# devboard-8_0.net
KiCad netlist of a schematic drawn in EAGLE
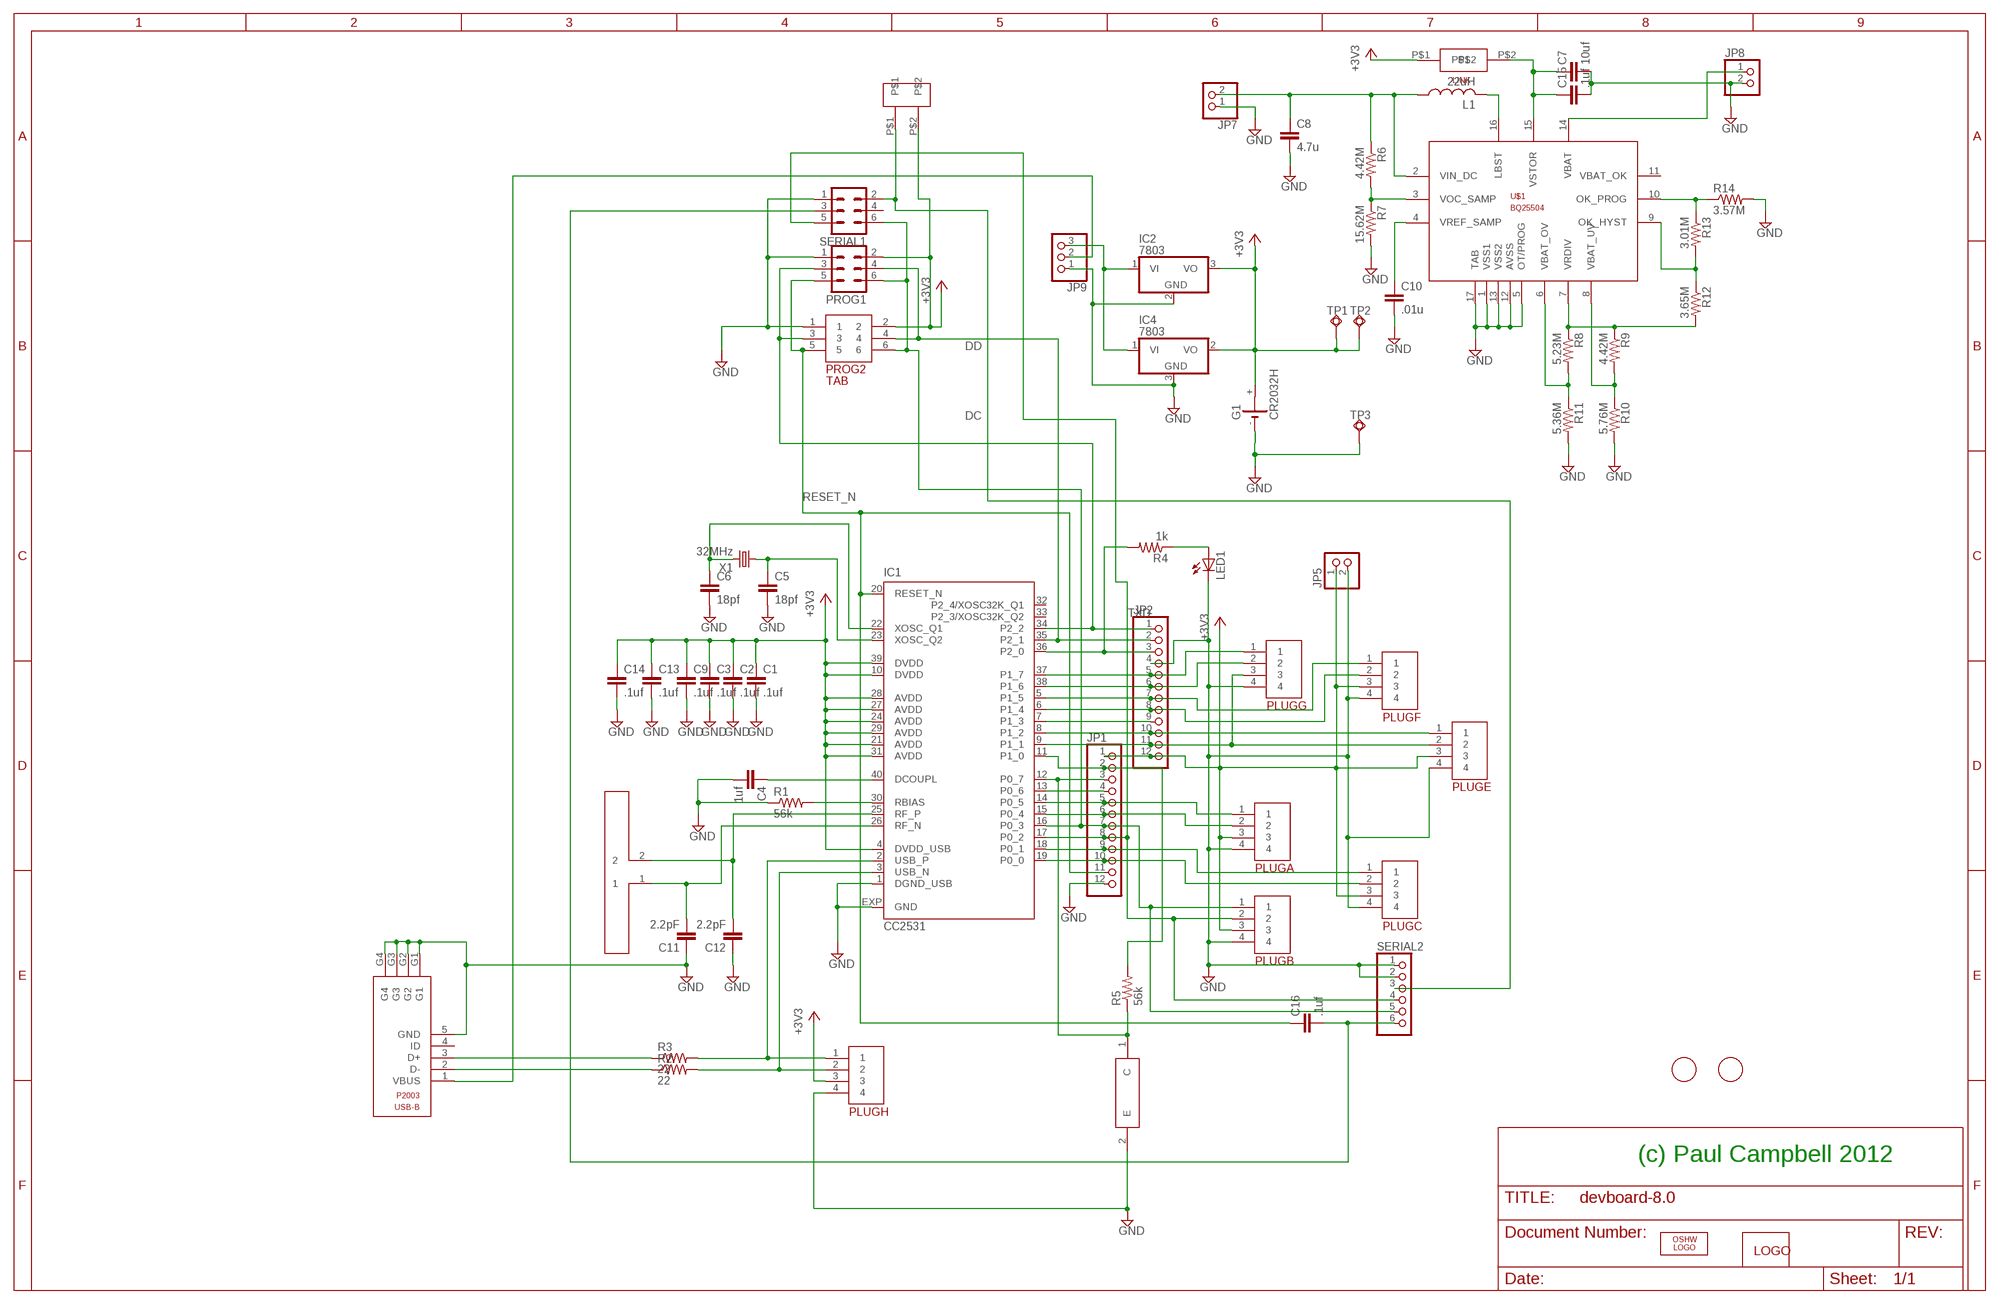
[diagram p0: schematic, sheet 1]

(export (version "E")
  (design (tool "Eeschema 10.0.6"))
  (components
    (comp (ref "C1")
      (value ".1uf")
      (footprint "eagle-import:C0603K")
      (libsource (lib "eagle-import") (part "C-EUC0603K"))
    )
    (comp (ref "C2")
      (value ".1uf")
      (footprint "eagle-import:C0603K")
      (libsource (lib "eagle-import") (part "C-EUC0603K"))
    )
    (comp (ref "C3")
      (value ".1uf")
      (footprint "eagle-import:C0603K")
      (libsource (lib "eagle-import") (part "C-EUC0603K"))
    )
    (comp (ref "C4")
      (value "1uf")
      (footprint "eagle-import:C0603K")
      (libsource (lib "eagle-import") (part "C-EUC0603K"))
    )
    (comp (ref "C5")
      (value "18pf")
      (footprint "eagle-import:C0603")
      (libsource (lib "eagle-import") (part "C-EUC0603"))
    )
    (comp (ref "C6")
      (value "18pf")
      (footprint "eagle-import:C0603")
      (libsource (lib "eagle-import") (part "C-EUC0603"))
    )
    (comp (ref "C7")
      (value "10uf")
      (footprint "eagle-import:C1206")
      (libsource (lib "eagle-import") (part "C-EUC1206"))
    )
    (comp (ref "C8")
      (value "4.7u")
      (footprint "eagle-import:C0603")
      (libsource (lib "eagle-import") (part "C-EUC0603"))
    )
    (comp (ref "C9")
      (value ".1uf")
      (footprint "eagle-import:C0603K")
      (libsource (lib "eagle-import") (part "C-EUC0603K"))
    )
    (comp (ref "C10")
      (value ".01u")
      (footprint "eagle-import:C0603")
      (libsource (lib "eagle-import") (part "C-EUC0603"))
    )
    (comp (ref "C11")
      (value "2.2pF")
      (footprint "eagle-import:C0402")
      (libsource (lib "eagle-import") (part "C-EUC0402"))
    )
    (comp (ref "C12")
      (value "2.2pF")
      (footprint "eagle-import:C0402")
      (libsource (lib "eagle-import") (part "C-EUC0402"))
    )
    (comp (ref "C13")
      (value ".1uf")
      (footprint "eagle-import:C0603K")
      (libsource (lib "eagle-import") (part "C-EUC0603K"))
    )
    (comp (ref "C14")
      (value ".1uf")
      (footprint "eagle-import:C0603K")
      (libsource (lib "eagle-import") (part "C-EUC0603K"))
    )
    (comp (ref "C15")
      (value ".1uf")
      (footprint "eagle-import:C0603K")
      (libsource (lib "eagle-import") (part "C-EUC0603K"))
    )
    (comp (ref "C16")
      (value ".1uf")
      (footprint "eagle-import:C0603K")
      (libsource (lib "eagle-import") (part "C-EUC0603K"))
    )
    (comp (ref "G1")
      (value "CR2032H")
      (footprint "eagle-import:CR2032H")
      (libsource (lib "eagle-import") (part "CR2032H"))
    )
    (comp (ref "IC1")
      (value "CC2531")
      (footprint "eagle-import:RHA_S-PVQFN-N40")
      (fields (field (name "MPN") "CC2531F256RHAT"))
      (libsource (lib "eagle-import") (part "CC2531"))
    )
    (comp (ref "IC2")
      (value "7803")
      (footprint "eagle-import:TO220V")
      (libsource (lib "eagle-import") (part "78TV05"))
    )
    (comp (ref "IC4")
      (value "7803")
      (footprint "eagle-import:TO252")
      (libsource (lib "eagle-import") (part "78DT05"))
    )
    (comp (ref "JP1")
      (value "PINHD-1X12-CB")
      (footprint "eagle-import:1X12-CB")
      (libsource (lib "eagle-import") (part "PINHD-1X12-CB"))
    )
    (comp (ref "JP2")
      (value "PINHD-1X12-CB")
      (footprint "eagle-import:1X12-CB")
      (libsource (lib "eagle-import") (part "PINHD-1X12-CB"))
    )
    (comp (ref "JP5")
      (value "PINHD-1X2")
      (footprint "eagle-import:1X02")
      (libsource (lib "eagle-import") (part "PINHD-1X2"))
    )
    (comp (ref "JP7")
      (value "PINHD-1X2")
      (footprint "eagle-import:1X02")
      (libsource (lib "eagle-import") (part "PINHD-1X2"))
    )
    (comp (ref "JP8")
      (value "PINHD-1X2")
      (footprint "eagle-import:1X02")
      (libsource (lib "eagle-import") (part "PINHD-1X2"))
    )
    (comp (ref "JP9")
      (value "PINHD-1X3")
      (footprint "eagle-import:1X03")
      (libsource (lib "eagle-import") (part "PINHD-1X3"))
    )
    (comp (ref "L1")
      (value "22uH")
      (footprint "eagle-import:L2012C")
      (libsource (lib "eagle-import") (part "L-USL2012C"))
    )
    (comp (ref "LED1")
      (value "LEDCHIP-LED0603")
      (footprint "eagle-import:CHIP-LED0603")
      (libsource (lib "eagle-import") (part "LEDCHIP-LED0603"))
    )
    (comp (ref "LOGO1")
      (value "OSHW_LOGO_FILLX0100-NT")
      (footprint "eagle-import:OSHW_FILLX100_NOTEXT")
      (libsource (lib "eagle-import") (part "OSHW_LOGO_FILLX0100-NT"))
    )
    (comp (ref "P2003")
      (value "FCI1018193-USBB")
      (footprint "eagle-import:FCI1018193-USBB")
      (libsource (lib "eagle-import") (part "FCI1018193-USBB"))
    )
    (comp (ref "PLUGA")
      (value "PIN4")
      (footprint "eagle-import:PIN4-2MM")
      (libsource (lib "eagle-import") (part "PIN4"))
    )
    (comp (ref "PLUGB")
      (value "PIN4")
      (footprint "eagle-import:PIN4-2MM")
      (libsource (lib "eagle-import") (part "PIN4"))
    )
    (comp (ref "PLUGC")
      (value "PIN4")
      (footprint "eagle-import:PIN4-2MM")
      (libsource (lib "eagle-import") (part "PIN4"))
    )
    (comp (ref "PLUGE")
      (value "PIN4")
      (footprint "eagle-import:PIN4-2MM")
      (libsource (lib "eagle-import") (part "PIN4"))
    )
    (comp (ref "PLUGF")
      (value "PIN4")
      (footprint "eagle-import:PIN4-2MM")
      (libsource (lib "eagle-import") (part "PIN4"))
    )
    (comp (ref "PLUGG")
      (value "PIN4")
      (footprint "eagle-import:PIN4-2MM")
      (libsource (lib "eagle-import") (part "PIN4"))
    )
    (comp (ref "PLUGH")
      (value "PIN4")
      (footprint "eagle-import:PIN4-2MM")
      (libsource (lib "eagle-import") (part "PIN4"))
    )
    (comp (ref "PROG1")
      (value "MA03-2")
      (footprint "eagle-import:MA03-2")
      (libsource (lib "eagle-import") (part "MA03-2"))
    )
    (comp (ref "PROG2")
      (value "TAB")
      (footprint "eagle-import:TAG")
      (libsource (lib "eagle-import") (part "TAB"))
    )
    (comp (ref "Q1")
      (value "KDT")
      (footprint "eagle-import:KDT")
      (libsource (lib "eagle-import") (part "KDT"))
    )
    (comp (ref "R1")
      (value "56k")
      (footprint "eagle-import:R0603")
      (libsource (lib "eagle-import") (part "R-US_R0603"))
    )
    (comp (ref "R2")
      (value "22")
      (footprint "eagle-import:R0603")
      (libsource (lib "eagle-import") (part "R-US_R0603"))
    )
    (comp (ref "R3")
      (value "22")
      (footprint "eagle-import:R0603")
      (libsource (lib "eagle-import") (part "R-US_R0603"))
    )
    (comp (ref "R4")
      (value "1k")
      (footprint "eagle-import:R0603")
      (libsource (lib "eagle-import") (part "R-US_R0603"))
    )
    (comp (ref "R5")
      (value "56k")
      (footprint "eagle-import:R0603")
      (libsource (lib "eagle-import") (part "R-US_R0603"))
    )
    (comp (ref "R6")
      (value "4.42M")
      (footprint "eagle-import:R0603")
      (libsource (lib "eagle-import") (part "R-US_R0603"))
    )
    (comp (ref "R7")
      (value "15.62M")
      (footprint "eagle-import:R0603")
      (libsource (lib "eagle-import") (part "R-US_R0603"))
    )
    (comp (ref "R8")
      (value "5.23M")
      (footprint "eagle-import:R0603")
      (libsource (lib "eagle-import") (part "R-US_R0603"))
    )
    (comp (ref "R9")
      (value "4.42M")
      (footprint "eagle-import:R0603")
      (libsource (lib "eagle-import") (part "R-US_R0603"))
    )
    (comp (ref "R10")
      (value "5.76M")
      (footprint "eagle-import:R0603")
      (libsource (lib "eagle-import") (part "R-US_R0603"))
    )
    (comp (ref "R11")
      (value "5.36M")
      (footprint "eagle-import:R0603")
      (libsource (lib "eagle-import") (part "R-US_R0603"))
    )
    (comp (ref "R12")
      (value "3.65M")
      (footprint "eagle-import:R0603")
      (libsource (lib "eagle-import") (part "R-US_R0603"))
    )
    (comp (ref "R13")
      (value "3.01M")
      (footprint "eagle-import:R0603")
      (libsource (lib "eagle-import") (part "R-US_R0603"))
    )
    (comp (ref "R14")
      (value "3.57M")
      (footprint "eagle-import:R0603")
      (libsource (lib "eagle-import") (part "R-US_R0603"))
    )
    (comp (ref "SERIAL-POWER")
      (value "2-PAD")
      (footprint "eagle-import:2-PAD")
      (libsource (lib "eagle-import") (part "2-PAD"))
    )
    (comp (ref "SERIAL1")
      (value "MA03-2")
      (footprint "eagle-import:MA03-2")
      (libsource (lib "eagle-import") (part "MA03-2"))
    )
    (comp (ref "SERIAL2")
      (value "PINHD-1X6")
      (footprint "eagle-import:1X06")
      (libsource (lib "eagle-import") (part "PINHD-1X6"))
    )
    (comp (ref "TP1")
      (value "TPSQPAD1-13")
      (footprint "eagle-import:P1-13")
      (libsource (lib "eagle-import") (part "TPSQPAD1-13"))
    )
    (comp (ref "TP2")
      (value "TPSQPAD1-13")
      (footprint "eagle-import:P1-13")
      (libsource (lib "eagle-import") (part "TPSQPAD1-13"))
    )
    (comp (ref "TP3")
      (value "TPSQPAD1-13")
      (footprint "eagle-import:P1-13")
      (libsource (lib "eagle-import") (part "TPSQPAD1-13"))
    )
    (comp (ref "U$1")
      (value "BQ25504")
      (footprint "eagle-import:QF16")
      (libsource (lib "eagle-import") (part "BQ25504"))
    )
    (comp (ref "U$2")
      (value "FIDUCIAL")
      (footprint "eagle-import:FIDUCIAL_1MM")
      (libsource (lib "eagle-import") (part "FIDUCIAL"))
    )
    (comp (ref "U$3")
      (value "DIPOLEDIPOLE1")
      (footprint "eagle-import:DIPOLE")
      (libsource (lib "eagle-import") (part "DIPOLEDIPOLE1"))
    )
    (comp (ref "U$4")
      (value "2-PAD-LINK")
      (footprint "eagle-import:2-PAD-LINK")
      (libsource (lib "eagle-import") (part "2-PAD-LINK"))
    )
    (comp (ref "U$5")
      (value "MOONBASE-LOGO")
      (footprint "eagle-import:MOONBASE-LOGO")
      (libsource (lib "eagle-import") (part "MOONBASE-LOGO"))
    )
    (comp (ref "U$18")
      (value "FIDUCIAL")
      (footprint "eagle-import:FIDUCIAL_1MM")
      (libsource (lib "eagle-import") (part "FIDUCIAL"))
    )
    (comp (ref "X1")
      (value "32MHz")
      (footprint "eagle-import:SM49")
      (libsource (lib "eagle-import") (part "CRYSTALSM49"))
    )
  )
  (nets
    (net (code "1") (name "+3V3") (class "Default")
      (node (ref "C1") (pin "1") (pinfunction "1_1") (pintype "passive"))
      (node (ref "C13") (pin "1") (pinfunction "1_1") (pintype "passive"))
      (node (ref "C14") (pin "1") (pinfunction "1_1") (pintype "passive"))
      (node (ref "C2") (pin "1") (pinfunction "1_1") (pintype "passive"))
      (node (ref "C3") (pin "1") (pinfunction "1_1") (pintype "passive"))
      (node (ref "C9") (pin "1") (pinfunction "1_1") (pintype "passive"))
      (node (ref "G1") (pin "+") (pinfunction "+_+") (pintype "passive"))
      (node (ref "IC1") (pin "10") (pinfunction "DVDD_10") (pintype "power_in"))
      (node (ref "IC1") (pin "21") (pinfunction "AVDD_21") (pintype "power_in"))
      (node (ref "IC1") (pin "24") (pinfunction "AVDD_24") (pintype "power_in"))
      (node (ref "IC1") (pin "27") (pinfunction "AVDD_27") (pintype "power_in"))
      (node (ref "IC1") (pin "28") (pinfunction "AVDD_28") (pintype "power_in"))
      (node (ref "IC1") (pin "29") (pinfunction "AVDD_29") (pintype "power_in"))
      (node (ref "IC1") (pin "31") (pinfunction "AVDD_31") (pintype "power_in"))
      (node (ref "IC1") (pin "39") (pinfunction "DVDD_39") (pintype "power_in"))
      (node (ref "IC1") (pin "4") (pinfunction "DVDD_USB_4") (pintype "power_in"))
      (node (ref "IC2") (pin "3") (pinfunction "VO_3") (pintype "passive"))
      (node (ref "IC4") (pin "2") (pinfunction "VO_2") (pintype "passive"))
      (node (ref "JP1") (pin "1") (pinfunction "1_1") (pintype "passive"))
      (node (ref "JP2") (pin "12") (pinfunction "12_12") (pintype "passive"))
      (node (ref "JP5") (pin "1") (pinfunction "1_1") (pintype "passive"))
      (node (ref "PLUGA") (pin "3") (pinfunction "3_3") (pintype "bidirectional"))
      (node (ref "PLUGB") (pin "3") (pinfunction "3_3") (pintype "bidirectional"))
      (node (ref "PLUGC") (pin "3") (pinfunction "3_3") (pintype "bidirectional"))
      (node (ref "PLUGE") (pin "3") (pinfunction "3_3") (pintype "bidirectional"))
      (node (ref "PLUGF") (pin "3") (pinfunction "3_3") (pintype "bidirectional"))
      (node (ref "PLUGH") (pin "3") (pinfunction "3_3") (pintype "bidirectional"))
      (node (ref "PROG1") (pin "2") (pinfunction "2_2") (pintype "passive"))
      (node (ref "PROG2") (pin "2") (pinfunction "2_2") (pintype "bidirectional"))
      (node (ref "SERIAL-POWER") (pin "P$2") (pinfunction "P$2_P$2") (pintype "bidirectional"))
      (node (ref "TP1") (pin "TP") (pinfunction "TP_TP") (pintype "input"))
      (node (ref "TP2") (pin "TP") (pinfunction "TP_TP") (pintype "input"))
      (node (ref "U$4") (pin "P$1") (pinfunction "P$1_P$1") (pintype "bidirectional"))
    )
    (net (code "2") (name "/DC") (class "Default")
      (node (ref "IC1") (pin "34") (pinfunction "P2_2_34") (pintype "bidirectional"))
      (node (ref "JP2") (pin "1") (pinfunction "1_1") (pintype "passive"))
      (node (ref "PROG1") (pin "3") (pinfunction "3_3") (pintype "passive"))
      (node (ref "PROG2") (pin "3") (pinfunction "3_3") (pintype "bidirectional"))
    )
    (net (code "3") (name "/DD") (class "Default")
      (node (ref "IC1") (pin "35") (pinfunction "P2_1_35") (pintype "bidirectional"))
      (node (ref "JP2") (pin "2") (pinfunction "2_2") (pintype "passive"))
      (node (ref "PROG1") (pin "4") (pinfunction "4_4") (pintype "passive"))
      (node (ref "PROG2") (pin "4") (pinfunction "4_4") (pintype "bidirectional"))
    )
    (net (code "4") (name "/RESET_N") (class "Default")
      (node (ref "C16") (pin "1") (pinfunction "1_1") (pintype "passive"))
      (node (ref "IC1") (pin "20") (pinfunction "RESET_N_20") (pintype "input"))
      (node (ref "JP1") (pin "11") (pinfunction "11_11") (pintype "passive"))
      (node (ref "PROG1") (pin "5") (pinfunction "5_5") (pintype "passive"))
      (node (ref "PROG2") (pin "5") (pinfunction "5_5") (pintype "bidirectional"))
    )
    (net (code "5") (name "/TXD") (class "Default")
      (node (ref "IC1") (pin "16") (pinfunction "P0_3_16") (pintype "bidirectional"))
      (node (ref "JP1") (pin "7") (pinfunction "7_7") (pintype "passive"))
      (node (ref "PLUGB") (pin "1") (pinfunction "1_1") (pintype "bidirectional"))
      (node (ref "PROG1") (pin "6") (pinfunction "6_6") (pintype "passive"))
      (node (ref "PROG2") (pin "6") (pinfunction "6_6") (pintype "bidirectional"))
      (node (ref "SERIAL1") (pin "6") (pinfunction "6_6") (pintype "passive"))
      (node (ref "SERIAL2") (pin "5") (pinfunction "5_5") (pintype "passive"))
    )
    (net (code "6") (name "GND") (class "Default")
      (node (ref "C1") (pin "2") (pinfunction "2_2") (pintype "passive"))
      (node (ref "C10") (pin "2") (pinfunction "2_2") (pintype "passive"))
      (node (ref "C11") (pin "1") (pinfunction "1_1") (pintype "passive"))
      (node (ref "C12") (pin "1") (pinfunction "1_1") (pintype "passive"))
      (node (ref "C13") (pin "2") (pinfunction "2_2") (pintype "passive"))
      (node (ref "C14") (pin "2") (pinfunction "2_2") (pintype "passive"))
      (node (ref "C15") (pin "2") (pinfunction "2_2") (pintype "passive"))
      (node (ref "C2") (pin "2") (pinfunction "2_2") (pintype "passive"))
      (node (ref "C3") (pin "2") (pinfunction "2_2") (pintype "passive"))
      (node (ref "C4") (pin "2") (pinfunction "2_2") (pintype "passive"))
      (node (ref "C5") (pin "2") (pinfunction "2_2") (pintype "passive"))
      (node (ref "C6") (pin "2") (pinfunction "2_2") (pintype "passive"))
      (node (ref "C7") (pin "2") (pinfunction "2_2") (pintype "passive"))
      (node (ref "C8") (pin "2") (pinfunction "2_2") (pintype "passive"))
      (node (ref "C9") (pin "2") (pinfunction "2_2") (pintype "passive"))
      (node (ref "G1") (pin "-") (pinfunction "-_-") (pintype "passive"))
      (node (ref "IC1") (pin "1") (pinfunction "DGND_USB_1") (pintype "power_in"))
      (node (ref "IC1") (pin "EXP") (pinfunction "GND_EXP") (pintype "passive"))
      (node (ref "IC2") (pin "2") (pinfunction "GND_2") (pintype "passive"))
      (node (ref "IC4") (pin "3") (pinfunction "GND_3") (pintype "passive"))
      (node (ref "JP1") (pin "12") (pinfunction "12_12") (pintype "passive"))
      (node (ref "JP2") (pin "4") (pinfunction "4_4") (pintype "passive"))
      (node (ref "JP5") (pin "2") (pinfunction "2_2") (pintype "passive"))
      (node (ref "JP7") (pin "1") (pinfunction "1_1") (pintype "passive"))
      (node (ref "JP8") (pin "2") (pinfunction "2_2") (pintype "passive"))
      (node (ref "JP9") (pin "1") (pinfunction "1_1") (pintype "passive"))
      (node (ref "LED1") (pin "C") (pinfunction "C_C") (pintype "passive"))
      (node (ref "P2003") (pin "5") (pinfunction "GND_5") (pintype "bidirectional"))
      (node (ref "P2003") (pin "G1") (pinfunction "G1_G1") (pintype "bidirectional"))
      (node (ref "P2003") (pin "G2") (pinfunction "G2_G2") (pintype "bidirectional"))
      (node (ref "P2003") (pin "G3") (pinfunction "G3_G3") (pintype "bidirectional"))
      (node (ref "P2003") (pin "G4") (pinfunction "G4_G4") (pintype "bidirectional"))
      (node (ref "PLUGA") (pin "4") (pinfunction "4_4") (pintype "bidirectional"))
      (node (ref "PLUGB") (pin "4") (pinfunction "4_4") (pintype "bidirectional"))
      (node (ref "PLUGC") (pin "4") (pinfunction "4_4") (pintype "bidirectional"))
      (node (ref "PLUGE") (pin "4") (pinfunction "4_4") (pintype "bidirectional"))
      (node (ref "PLUGF") (pin "4") (pinfunction "4_4") (pintype "bidirectional"))
      (node (ref "PLUGG") (pin "4") (pinfunction "4_4") (pintype "bidirectional"))
      (node (ref "PLUGH") (pin "4") (pinfunction "4_4") (pintype "bidirectional"))
      (node (ref "PROG1") (pin "1") (pinfunction "1_1") (pintype "passive"))
      (node (ref "PROG2") (pin "1") (pinfunction "1_1") (pintype "bidirectional"))
      (node (ref "Q1") (pin "2") (pinfunction "E_2") (pintype "bidirectional"))
      (node (ref "R1") (pin "1") (pinfunction "1_1") (pintype "passive"))
      (node (ref "R10") (pin "2") (pinfunction "2_2") (pintype "passive"))
      (node (ref "R11") (pin "2") (pinfunction "2_2") (pintype "passive"))
      (node (ref "R14") (pin "2") (pinfunction "2_2") (pintype "passive"))
      (node (ref "R7") (pin "2") (pinfunction "2_2") (pintype "passive"))
      (node (ref "SERIAL1") (pin "1") (pinfunction "1_1") (pintype "passive"))
      (node (ref "SERIAL2") (pin "1") (pinfunction "1_1") (pintype "passive"))
      (node (ref "SERIAL2") (pin "2") (pinfunction "2_2") (pintype "passive"))
      (node (ref "TP3") (pin "TP") (pinfunction "TP_TP") (pintype "input"))
      (node (ref "U$1") (pin "1") (pinfunction "VSS1_1") (pintype "bidirectional"))
      (node (ref "U$1") (pin "12") (pinfunction "AVSS_12") (pintype "bidirectional"))
      (node (ref "U$1") (pin "13") (pinfunction "VSS2_13") (pintype "bidirectional"))
      (node (ref "U$1") (pin "17") (pinfunction "TAB_17") (pintype "bidirectional"))
      (node (ref "U$1") (pin "5") (pinfunction "OT/PROG_5") (pintype "bidirectional"))
    )
    (net (code "7") (name "Net-(C16-Pad2)") (class "Default")
      (node (ref "C16") (pin "2") (pinfunction "2_2") (pintype "passive"))
      (node (ref "SERIAL1") (pin "3") (pinfunction "3_3") (pintype "passive"))
      (node (ref "SERIAL2") (pin "6") (pinfunction "6_6") (pintype "passive"))
    )
    (net (code "8") (name "Net-(IC1-DCOUPL)") (class "Default")
      (node (ref "C4") (pin "1") (pinfunction "1_1") (pintype "passive"))
      (node (ref "IC1") (pin "40") (pinfunction "DCOUPL_40") (pintype "power_in"))
    )
    (net (code "9") (name "Net-(IC1-P0_0)") (class "Default")
      (node (ref "IC1") (pin "19") (pinfunction "P0_0_19") (pintype "bidirectional"))
      (node (ref "JP1") (pin "10") (pinfunction "10_10") (pintype "passive"))
      (node (ref "PLUGC") (pin "2") (pinfunction "2_2") (pintype "bidirectional"))
    )
    (net (code "10") (name "Net-(IC1-P0_1)") (class "Default")
      (node (ref "IC1") (pin "18") (pinfunction "P0_1_18") (pintype "bidirectional"))
      (node (ref "JP1") (pin "9") (pinfunction "9_9") (pintype "passive"))
      (node (ref "PLUGC") (pin "1") (pinfunction "1_1") (pintype "bidirectional"))
    )
    (net (code "11") (name "Net-(IC1-P0_2)") (class "Default")
      (node (ref "IC1") (pin "17") (pinfunction "P0_2_17") (pintype "bidirectional"))
      (node (ref "JP1") (pin "8") (pinfunction "8_8") (pintype "passive"))
      (node (ref "PLUGB") (pin "2") (pinfunction "2_2") (pintype "bidirectional"))
      (node (ref "SERIAL1") (pin "5") (pinfunction "5_5") (pintype "passive"))
      (node (ref "SERIAL2") (pin "4") (pinfunction "4_4") (pintype "passive"))
    )
    (net (code "12") (name "Net-(IC1-P0_4)") (class "Default")
      (node (ref "IC1") (pin "15") (pinfunction "P0_4_15") (pintype "bidirectional"))
      (node (ref "JP1") (pin "6") (pinfunction "6_6") (pintype "passive"))
      (node (ref "PLUGA") (pin "2") (pinfunction "2_2") (pintype "bidirectional"))
    )
    (net (code "13") (name "Net-(IC1-P0_5)") (class "Default")
      (node (ref "IC1") (pin "14") (pinfunction "P0_5_14") (pintype "bidirectional"))
      (node (ref "JP1") (pin "5") (pinfunction "5_5") (pintype "passive"))
      (node (ref "PLUGA") (pin "1") (pinfunction "1_1") (pintype "bidirectional"))
    )
    (net (code "14") (name "Net-(IC1-P0_6)") (class "Default")
      (node (ref "IC1") (pin "13") (pinfunction "P0_6_13") (pintype "bidirectional"))
      (node (ref "JP1") (pin "4") (pinfunction "4_4") (pintype "passive"))
    )
    (net (code "15") (name "Net-(IC1-P0_7)") (class "Default")
      (node (ref "IC1") (pin "12") (pinfunction "P0_7_12") (pintype "bidirectional"))
      (node (ref "JP1") (pin "3") (pinfunction "3_3") (pintype "passive"))
      (node (ref "Q1") (pin "1") (pinfunction "C_1") (pintype "bidirectional"))
      (node (ref "R5") (pin "1") (pinfunction "1_1") (pintype "passive"))
    )
    (net (code "16") (name "Net-(IC1-P1_0)") (class "Default")
      (node (ref "IC1") (pin "11") (pinfunction "P1_0_11") (pintype "bidirectional"))
      (node (ref "JP1") (pin "2") (pinfunction "2_2") (pintype "passive"))
      (node (ref "R5") (pin "2") (pinfunction "2_2") (pintype "passive"))
    )
    (net (code "17") (name "Net-(IC1-P1_1)") (class "Default")
      (node (ref "IC1") (pin "9") (pinfunction "P1_1_9") (pintype "bidirectional"))
      (node (ref "JP2") (pin "11") (pinfunction "11_11") (pintype "passive"))
      (node (ref "PLUGE") (pin "2") (pinfunction "2_2") (pintype "bidirectional"))
      (node (ref "PLUGG") (pin "3") (pinfunction "3_3") (pintype "bidirectional"))
    )
    (net (code "18") (name "Net-(IC1-P1_2)") (class "Default")
      (node (ref "IC1") (pin "8") (pinfunction "P1_2_8") (pintype "bidirectional"))
      (node (ref "JP2") (pin "10") (pinfunction "10_10") (pintype "passive"))
      (node (ref "PLUGE") (pin "1") (pinfunction "1_1") (pintype "bidirectional"))
    )
    (net (code "19") (name "Net-(IC1-P1_3)") (class "Default")
      (node (ref "IC1") (pin "7") (pinfunction "P1_3_7") (pintype "bidirectional"))
      (node (ref "JP2") (pin "9") (pinfunction "9_9") (pintype "passive"))
    )
    (net (code "20") (name "Net-(IC1-P1_4)") (class "Default")
      (node (ref "IC1") (pin "6") (pinfunction "P1_4_6") (pintype "bidirectional"))
      (node (ref "JP2") (pin "8") (pinfunction "8_8") (pintype "passive"))
      (node (ref "PLUGF") (pin "2") (pinfunction "2_2") (pintype "bidirectional"))
    )
    (net (code "21") (name "Net-(IC1-P1_5)") (class "Default")
      (node (ref "IC1") (pin "5") (pinfunction "P1_5_5") (pintype "bidirectional"))
      (node (ref "JP2") (pin "7") (pinfunction "7_7") (pintype "passive"))
      (node (ref "PLUGF") (pin "1") (pinfunction "1_1") (pintype "bidirectional"))
    )
    (net (code "22") (name "Net-(IC1-P1_6)") (class "Default")
      (node (ref "IC1") (pin "38") (pinfunction "P1_6_38") (pintype "bidirectional"))
      (node (ref "JP2") (pin "6") (pinfunction "6_6") (pintype "passive"))
      (node (ref "PLUGG") (pin "2") (pinfunction "2_2") (pintype "bidirectional"))
    )
    (net (code "23") (name "Net-(IC1-P1_7)") (class "Default")
      (node (ref "IC1") (pin "37") (pinfunction "P1_7_37") (pintype "bidirectional"))
      (node (ref "JP2") (pin "5") (pinfunction "5_5") (pintype "passive"))
      (node (ref "PLUGG") (pin "1") (pinfunction "1_1") (pintype "bidirectional"))
    )
    (net (code "24") (name "Net-(IC1-P2_0)") (class "Default")
      (node (ref "IC1") (pin "36") (pinfunction "P2_0_36") (pintype "bidirectional"))
      (node (ref "JP2") (pin "3") (pinfunction "3_3") (pintype "passive"))
      (node (ref "R4") (pin "2") (pinfunction "2_2") (pintype "passive"))
    )
    (net (code "25") (name "Net-(IC1-RBIAS)") (class "Default")
      (node (ref "IC1") (pin "30") (pinfunction "RBIAS_30") (pintype "bidirectional"))
      (node (ref "R1") (pin "2") (pinfunction "2_2") (pintype "passive"))
    )
    (net (code "26") (name "Net-(IC1-RF_N)") (class "Default")
      (node (ref "C11") (pin "2") (pinfunction "2_2") (pintype "passive"))
      (node (ref "IC1") (pin "26") (pinfunction "RF_N_26") (pintype "bidirectional"))
      (node (ref "U$3") (pin "1") (pinfunction "1_1") (pintype "bidirectional"))
    )
    (net (code "27") (name "Net-(IC1-RF_P)") (class "Default")
      (node (ref "C12") (pin "2") (pinfunction "2_2") (pintype "passive"))
      (node (ref "IC1") (pin "25") (pinfunction "RF_P_25") (pintype "bidirectional"))
      (node (ref "U$3") (pin "2") (pinfunction "2_2") (pintype "bidirectional"))
    )
    (net (code "28") (name "Net-(IC1-USB_N)") (class "Default")
      (node (ref "IC1") (pin "3") (pinfunction "USB_N_3") (pintype "bidirectional"))
      (node (ref "PLUGH") (pin "2") (pinfunction "2_2") (pintype "bidirectional"))
      (node (ref "R2") (pin "2") (pinfunction "2_2") (pintype "passive"))
    )
    (net (code "29") (name "Net-(IC1-USB_P)") (class "Default")
      (node (ref "IC1") (pin "2") (pinfunction "USB_P_2") (pintype "bidirectional"))
      (node (ref "PLUGH") (pin "1") (pinfunction "1_1") (pintype "bidirectional"))
      (node (ref "R3") (pin "2") (pinfunction "2_2") (pintype "passive"))
    )
    (net (code "30") (name "Net-(IC1-XOSC_Q1)") (class "Default")
      (node (ref "C6") (pin "1") (pinfunction "1_1") (pintype "passive"))
      (node (ref "IC1") (pin "22") (pinfunction "XOSC_Q1_22") (pintype "bidirectional"))
      (node (ref "X1") (pin "2") (pinfunction "2_2") (pintype "passive"))
    )
    (net (code "31") (name "Net-(IC1-XOSC_Q2)") (class "Default")
      (node (ref "C5") (pin "1") (pinfunction "1_1") (pintype "passive"))
      (node (ref "IC1") (pin "23") (pinfunction "XOSC_Q2_23") (pintype "bidirectional"))
      (node (ref "X1") (pin "1") (pinfunction "1_1") (pintype "passive"))
    )
    (net (code "32") (name "Net-(IC2-VI)") (class "Default")
      (node (ref "IC2") (pin "1") (pinfunction "VI_1") (pintype "input"))
      (node (ref "IC4") (pin "1") (pinfunction "VI_1") (pintype "input"))
      (node (ref "JP9") (pin "3") (pinfunction "3_3") (pintype "passive"))
    )
    (net (code "33") (name "Net-(LED1-PadA)") (class "Default")
      (node (ref "LED1") (pin "A") (pinfunction "A_A") (pintype "passive"))
      (node (ref "R4") (pin "1") (pinfunction "1_1") (pintype "passive"))
    )
    (net (code "34") (name "Net-(P2003-D+)") (class "Default")
      (node (ref "P2003") (pin "3") (pinfunction "D+_3") (pintype "bidirectional"))
      (node (ref "R3") (pin "1") (pinfunction "1_1") (pintype "passive"))
    )
    (net (code "35") (name "Net-(P2003-D-)") (class "Default")
      (node (ref "P2003") (pin "2") (pinfunction "D-_2") (pintype "bidirectional"))
      (node (ref "R2") (pin "1") (pinfunction "1_1") (pintype "passive"))
    )
    (net (code "36") (name "Net-(P2003-VBUS)") (class "Default")
      (node (ref "JP9") (pin "2") (pinfunction "2_2") (pintype "passive"))
      (node (ref "P2003") (pin "1") (pinfunction "VBUS_1") (pintype "bidirectional"))
    )
    (net (code "37") (name "Net-(SERIAL-POWER-PadP$1)") (class "Default")
      (node (ref "SERIAL-POWER") (pin "P$1") (pinfunction "P$1_P$1") (pintype "bidirectional"))
      (node (ref "SERIAL1") (pin "2") (pinfunction "2_2") (pintype "passive"))
      (node (ref "SERIAL2") (pin "3") (pinfunction "3_3") (pintype "passive"))
    )
    (net (code "38") (name "Net-(U$1-LBST)") (class "Default")
      (node (ref "L1") (pin "2") (pinfunction "2_2") (pintype "passive"))
      (node (ref "U$1") (pin "16") (pinfunction "LBST_16") (pintype "bidirectional"))
    )
    (net (code "39") (name "Net-(U$1-OK_HYST)") (class "Default")
      (node (ref "R12") (pin "1") (pinfunction "1_1") (pintype "passive"))
      (node (ref "R13") (pin "2") (pinfunction "2_2") (pintype "passive"))
      (node (ref "U$1") (pin "9") (pinfunction "OK_HYST_9") (pintype "bidirectional"))
    )
    (net (code "40") (name "Net-(U$1-OK_PROG)") (class "Default")
      (node (ref "R13") (pin "1") (pinfunction "1_1") (pintype "passive"))
      (node (ref "R14") (pin "1") (pinfunction "1_1") (pintype "passive"))
      (node (ref "U$1") (pin "10") (pinfunction "OK_PROG_10") (pintype "bidirectional"))
    )
    (net (code "41") (name "Net-(U$1-VBAT)") (class "Default")
      (node (ref "JP8") (pin "1") (pinfunction "1_1") (pintype "passive"))
      (node (ref "U$1") (pin "14") (pinfunction "VBAT_14") (pintype "bidirectional"))
    )
    (net (code "42") (name "Net-(U$1-VBAT_OV)") (class "Default")
      (node (ref "R11") (pin "1") (pinfunction "1_1") (pintype "passive"))
      (node (ref "R8") (pin "2") (pinfunction "2_2") (pintype "passive"))
      (node (ref "U$1") (pin "6") (pinfunction "VBAT_OV_6") (pintype "bidirectional"))
    )
    (net (code "43") (name "Net-(U$1-VBAT_UV)") (class "Default")
      (node (ref "R10") (pin "1") (pinfunction "1_1") (pintype "passive"))
      (node (ref "R9") (pin "2") (pinfunction "2_2") (pintype "passive"))
      (node (ref "U$1") (pin "8") (pinfunction "VBAT_UV_8") (pintype "bidirectional"))
    )
    (net (code "44") (name "Net-(U$1-VIN_DC)") (class "Default")
      (node (ref "C8") (pin "1") (pinfunction "1_1") (pintype "passive"))
      (node (ref "JP7") (pin "2") (pinfunction "2_2") (pintype "passive"))
      (node (ref "L1") (pin "1") (pinfunction "1_1") (pintype "passive"))
      (node (ref "R6") (pin "1") (pinfunction "1_1") (pintype "passive"))
      (node (ref "U$1") (pin "2") (pinfunction "VIN_DC_2") (pintype "bidirectional"))
    )
    (net (code "45") (name "Net-(U$1-VOC_SAMP)") (class "Default")
      (node (ref "R6") (pin "2") (pinfunction "2_2") (pintype "passive"))
      (node (ref "R7") (pin "1") (pinfunction "1_1") (pintype "passive"))
      (node (ref "U$1") (pin "3") (pinfunction "VOC_SAMP_3") (pintype "bidirectional"))
    )
    (net (code "46") (name "Net-(U$1-VRDIV)") (class "Default")
      (node (ref "R12") (pin "2") (pinfunction "2_2") (pintype "passive"))
      (node (ref "R8") (pin "1") (pinfunction "1_1") (pintype "passive"))
      (node (ref "R9") (pin "1") (pinfunction "1_1") (pintype "passive"))
      (node (ref "U$1") (pin "7") (pinfunction "VRDIV_7") (pintype "bidirectional"))
    )
    (net (code "47") (name "Net-(U$1-VREF_SAMP)") (class "Default")
      (node (ref "C10") (pin "1") (pinfunction "1_1") (pintype "passive"))
      (node (ref "U$1") (pin "4") (pinfunction "VREF_SAMP_4") (pintype "bidirectional"))
    )
    (net (code "48") (name "Net-(U$1-VSTOR)") (class "Default")
      (node (ref "C15") (pin "1") (pinfunction "1_1") (pintype "passive"))
      (node (ref "C7") (pin "1") (pinfunction "1_1") (pintype "passive"))
      (node (ref "U$1") (pin "15") (pinfunction "VSTOR_15") (pintype "bidirectional"))
      (node (ref "U$4") (pin "P$2") (pinfunction "P$2_P$2") (pintype "bidirectional"))
    )
    (net (code "49") (name "unconnected-(G1-+-Pad+@1)") (class "Default")
      (node (ref "G1") (pin "+@1") (pinfunction "+_+@1") (pintype "passive"))
    )
    (net (code "50") (name "unconnected-(IC1-P2_3{slash}XOSC32K_Q2-Pad33)") (class "Default")
      (node (ref "IC1") (pin "33") (pinfunction "P2_3/XOSC32K_Q2_33") (pintype "bidirectional"))
    )
    (net (code "51") (name "unconnected-(IC1-P2_4{slash}XOSC32K_Q1-Pad32)") (class "Default")
      (node (ref "IC1") (pin "32") (pinfunction "P2_4/XOSC32K_Q1_32") (pintype "bidirectional"))
    )
    (net (code "52") (name "unconnected-(P2003-ID-Pad4)") (class "Default")
      (node (ref "P2003") (pin "4") (pinfunction "ID_4") (pintype "bidirectional"))
    )
    (net (code "53") (name "unconnected-(SERIAL1-Pad4)") (class "Default")
      (node (ref "SERIAL1") (pin "4") (pinfunction "4_4") (pintype "passive"))
    )
    (net (code "54") (name "unconnected-(U$1-VBAT_OK-Pad11)") (class "Default")
      (node (ref "U$1") (pin "11") (pinfunction "VBAT_OK_11") (pintype "bidirectional"))
    )
  )
)
